# base-1.net
KiCad netlist of a schematic drawn in EAGLE
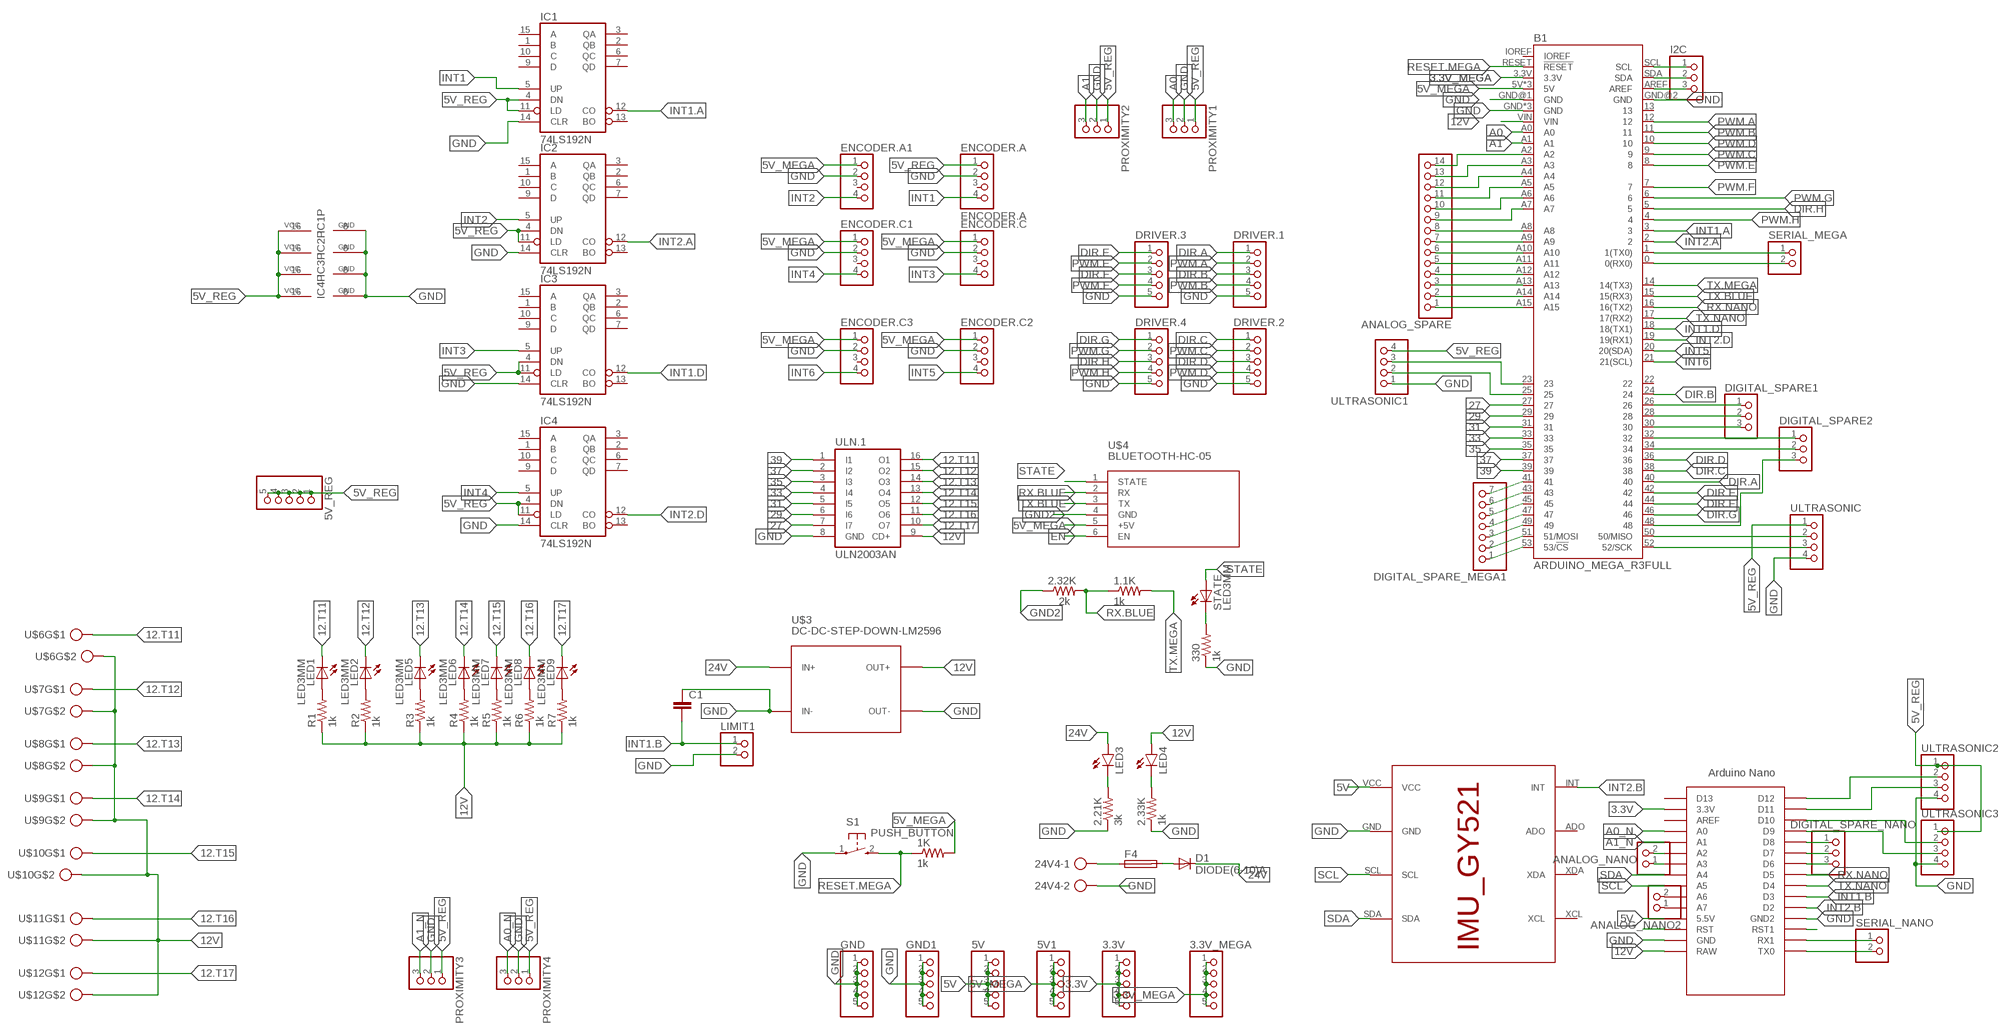
[diagram p0: schematic, sheet 1]

(export (version "E")
  (design (tool "Eeschema 10.0.6"))
  (components
    (comp (ref "1.1K")
      (value "1k")
      (footprint "eagle-import:0204_5")
      (libsource (lib "eagle-import") (part "RES-5"))
    )
    (comp (ref "1K")
      (value "1k")
      (footprint "eagle-import:0204_5")
      (libsource (lib "eagle-import") (part "RES-5"))
    )
    (comp (ref "2.21K")
      (value "3k")
      (footprint "eagle-import:0204_5")
      (libsource (lib "eagle-import") (part "RES-5"))
    )
    (comp (ref "2.32K")
      (value "2k")
      (footprint "eagle-import:0204_5")
      (libsource (lib "eagle-import") (part "RES-5"))
    )
    (comp (ref "2.33K")
      (value "1k")
      (footprint "eagle-import:0204_5")
      (libsource (lib "eagle-import") (part "RES-5"))
    )
    (comp (ref "3.3V")
      (value "PINHD-1X5")
      (footprint "eagle-import:1X05")
      (libsource (lib "eagle-import") (part "PINHD-1X5"))
    )
    (comp (ref "3.3V_MEGA")
      (value "PINHD-1X5")
      (footprint "eagle-import:1X05")
      (libsource (lib "eagle-import") (part "PINHD-1X5"))
    )
    (comp (ref "5V")
      (value "PINHD-1X5")
      (footprint "eagle-import:1X05")
      (libsource (lib "eagle-import") (part "PINHD-1X5"))
    )
    (comp (ref "5V1")
      (value "PINHD-1X5")
      (footprint "eagle-import:1X05")
      (libsource (lib "eagle-import") (part "PINHD-1X5"))
    )
    (comp (ref "5V_REG")
      (value "PINHD-1X5")
      (footprint "eagle-import:1X05")
      (libsource (lib "eagle-import") (part "PINHD-1X5"))
    )
    (comp (ref "24V4")
      (value "ROSTA.POWER")
      (footprint "eagle-import:W239-302")
      (libsource (lib "eagle-import") (part "ROSTA.POWER"))
    )
    (comp (ref "330")
      (value "1k")
      (footprint "eagle-import:0204_5")
      (libsource (lib "eagle-import") (part "RES-5"))
    )
    (comp (ref "ANALOG_NANO")
      (value "PINHD-1X2")
      (footprint "eagle-import:1X02")
      (libsource (lib "eagle-import") (part "PINHD-1X2"))
    )
    (comp (ref "ANALOG_NANO2")
      (value "PINHD-1X2")
      (footprint "eagle-import:1X02")
      (libsource (lib "eagle-import") (part "PINHD-1X2"))
    )
    (comp (ref "ANALOG_SPARE")
      (value "PINHD-1X14")
      (footprint "eagle-import:1X14")
      (libsource (lib "eagle-import") (part "PINHD-1X14"))
    )
    (comp (ref "B1")
      (value "ARDUINO_MEGA_R3FULL")
      (footprint "eagle-import:ARDUINO_MEGA_NO_SILK")
      (libsource (lib "eagle-import") (part "ARDUINO_MEGA_R3FULL"))
    )
    (comp (ref "C1")
      (value "CAPACITOR")
      (footprint "eagle-import:C025-025X050")
      (libsource (lib "eagle-import") (part "CAPACITOR"))
    )
    (comp (ref "D1")
      (value "DIODE(6-10)A")
      (footprint "eagle-import:DO201-15")
      (libsource (lib "eagle-import") (part "DIODE(6-10)A"))
    )
    (comp (ref "DIGITAL_SPARE1")
      (value "PINHD-1X3")
      (footprint "eagle-import:1X03")
      (libsource (lib "eagle-import") (part "PINHD-1X3"))
    )
    (comp (ref "DIGITAL_SPARE2")
      (value "PINHD-1X3")
      (footprint "eagle-import:1X03")
      (libsource (lib "eagle-import") (part "PINHD-1X3"))
    )
    (comp (ref "DIGITAL_SPARE_MEGA1")
      (value "PINHD-1X7")
      (footprint "eagle-import:1X07")
      (libsource (lib "eagle-import") (part "PINHD-1X7"))
    )
    (comp (ref "DIGITAL_SPARE_NANO")
      (value "PINHD-1X3")
      (footprint "eagle-import:1X03")
      (libsource (lib "eagle-import") (part "PINHD-1X3"))
    )
    (comp (ref "DRIVER.1")
      (value "PINHD-1X5")
      (footprint "eagle-import:1X05")
      (libsource (lib "eagle-import") (part "PINHD-1X5"))
    )
    (comp (ref "DRIVER.2")
      (value "PINHD-1X5")
      (footprint "eagle-import:1X05")
      (libsource (lib "eagle-import") (part "PINHD-1X5"))
    )
    (comp (ref "DRIVER.3")
      (value "PINHD-1X5")
      (footprint "eagle-import:1X05")
      (libsource (lib "eagle-import") (part "PINHD-1X5"))
    )
    (comp (ref "DRIVER.4")
      (value "PINHD-1X5")
      (footprint "eagle-import:1X05")
      (libsource (lib "eagle-import") (part "PINHD-1X5"))
    )
    (comp (ref "ENCODER.A")
      (value "ENCODER.A")
      (footprint "eagle-import:1X04")
      (libsource (lib "eagle-import") (part "PINHD-1X4"))
    )
    (comp (ref "ENCODER.A1")
      (value "PINHD-1X4")
      (footprint "eagle-import:1X04")
      (libsource (lib "eagle-import") (part "PINHD-1X4"))
    )
    (comp (ref "ENCODER.C")
      (value "PINHD-1X4")
      (footprint "eagle-import:1X04")
      (libsource (lib "eagle-import") (part "PINHD-1X4"))
    )
    (comp (ref "ENCODER.C1")
      (value "PINHD-1X4")
      (footprint "eagle-import:1X04")
      (libsource (lib "eagle-import") (part "PINHD-1X4"))
    )
    (comp (ref "ENCODER.C2")
      (value "PINHD-1X4")
      (footprint "eagle-import:1X04")
      (libsource (lib "eagle-import") (part "PINHD-1X4"))
    )
    (comp (ref "ENCODER.C3")
      (value "PINHD-1X4")
      (footprint "eagle-import:1X04")
      (libsource (lib "eagle-import") (part "PINHD-1X4"))
    )
    (comp (ref "F4")
      (value "FUSE_HOLDER")
      (footprint "eagle-import:SH22,5A")
      (libsource (lib "eagle-import") (part "FUSE_HOLDER"))
    )
    (comp (ref "GND")
      (value "PINHD-1X5")
      (footprint "eagle-import:1X05")
      (libsource (lib "eagle-import") (part "PINHD-1X5"))
    )
    (comp (ref "GND1")
      (value "PINHD-1X5")
      (footprint "eagle-import:1X05")
      (libsource (lib "eagle-import") (part "PINHD-1X5"))
    )
    (comp (ref "I2C")
      (value "PINHD-1X3")
      (footprint "eagle-import:1X03")
      (libsource (lib "eagle-import") (part "PINHD-1X3"))
    )
    (comp (ref "IC1")
      (value "74LS192N")
      (footprint "eagle-import:DIL16")
      (libsource (lib "eagle-import") (part "74192NLS"))
    )
    (comp (ref "IC2")
      (value "74LS192N")
      (footprint "eagle-import:DIL16")
      (libsource (lib "eagle-import") (part "74192NLS"))
    )
    (comp (ref "IC3")
      (value "74LS192N")
      (footprint "eagle-import:DIL16")
      (libsource (lib "eagle-import") (part "74192NLS"))
    )
    (comp (ref "IC4")
      (value "74LS192N")
      (footprint "eagle-import:DIL16")
      (libsource (lib "eagle-import") (part "74192NLS"))
    )
    (comp (ref "LED1")
      (value "LED3MM")
      (footprint "eagle-import:LED3MM")
      (libsource (lib "eagle-import") (part "LED3MM"))
    )
    (comp (ref "LED2")
      (value "LED3MM")
      (footprint "eagle-import:LED3MM")
      (libsource (lib "eagle-import") (part "LED3MM"))
    )
    (comp (ref "LED3")
      (value "LED5MM")
      (footprint "eagle-import:LED5MM")
      (libsource (lib "eagle-import") (part "LED5MM"))
    )
    (comp (ref "LED4")
      (value "LED5MM")
      (footprint "eagle-import:LED5MM")
      (libsource (lib "eagle-import") (part "LED5MM"))
    )
    (comp (ref "LED5")
      (value "LED3MM")
      (footprint "eagle-import:LED3MM")
      (libsource (lib "eagle-import") (part "LED3MM"))
    )
    (comp (ref "LED6")
      (value "LED3MM")
      (footprint "eagle-import:LED3MM")
      (libsource (lib "eagle-import") (part "LED3MM"))
    )
    (comp (ref "LED7")
      (value "LED3MM")
      (footprint "eagle-import:LED3MM")
      (libsource (lib "eagle-import") (part "LED3MM"))
    )
    (comp (ref "LED8")
      (value "LED3MM")
      (footprint "eagle-import:LED3MM")
      (libsource (lib "eagle-import") (part "LED3MM"))
    )
    (comp (ref "LED9")
      (value "LED3MM")
      (footprint "eagle-import:LED3MM")
      (libsource (lib "eagle-import") (part "LED3MM"))
    )
    (comp (ref "LIMIT1")
      (value "PINHD-1X2")
      (footprint "eagle-import:1X02")
      (libsource (lib "eagle-import") (part "PINHD-1X2"))
    )
    (comp (ref "PROXIMITY1")
      (value "PINHD-1X3")
      (footprint "eagle-import:1X03")
      (libsource (lib "eagle-import") (part "PINHD-1X3"))
    )
    (comp (ref "PROXIMITY2")
      (value "PINHD-1X3")
      (footprint "eagle-import:1X03")
      (libsource (lib "eagle-import") (part "PINHD-1X3"))
    )
    (comp (ref "PROXIMITY3")
      (value "PINHD-1X3")
      (footprint "eagle-import:1X03")
      (libsource (lib "eagle-import") (part "PINHD-1X3"))
    )
    (comp (ref "PROXIMITY4")
      (value "PINHD-1X3")
      (footprint "eagle-import:1X03")
      (libsource (lib "eagle-import") (part "PINHD-1X3"))
    )
    (comp (ref "R1")
      (value "1k")
      (footprint "eagle-import:0204_5")
      (libsource (lib "eagle-import") (part "RES-5"))
    )
    (comp (ref "R2")
      (value "1k")
      (footprint "eagle-import:0204_5")
      (libsource (lib "eagle-import") (part "RES-5"))
    )
    (comp (ref "R3")
      (value "1k")
      (footprint "eagle-import:0204_5")
      (libsource (lib "eagle-import") (part "RES-5"))
    )
    (comp (ref "R4")
      (value "1k")
      (footprint "eagle-import:0204_5")
      (libsource (lib "eagle-import") (part "RES-5"))
    )
    (comp (ref "R5")
      (value "1k")
      (footprint "eagle-import:0204_5")
      (libsource (lib "eagle-import") (part "RES-5"))
    )
    (comp (ref "R6")
      (value "1k")
      (footprint "eagle-import:0204_5")
      (libsource (lib "eagle-import") (part "RES-5"))
    )
    (comp (ref "R7")
      (value "1k")
      (footprint "eagle-import:0204_5")
      (libsource (lib "eagle-import") (part "RES-5"))
    )
    (comp (ref "S1")
      (value "PUSH_BUTTON")
      (footprint "eagle-import:B3F-10XX")
      (libsource (lib "eagle-import") (part "PUSH_BUTTON"))
    )
    (comp (ref "SERIAL_MEGA")
      (value "PINHD-1X2")
      (footprint "eagle-import:1X02")
      (libsource (lib "eagle-import") (part "PINHD-1X2"))
    )
    (comp (ref "SERIAL_NANO")
      (value "PINHD-1X2")
      (footprint "eagle-import:1X02")
      (libsource (lib "eagle-import") (part "PINHD-1X2"))
    )
    (comp (ref "STATE")
      (value "LED3MM")
      (footprint "eagle-import:LED3MM")
      (libsource (lib "eagle-import") (part "LED3MM"))
    )
    (comp (ref "U$1")
      (value "ARDUINO_NANO")
      (footprint "eagle-import:NANO")
      (libsource (lib "eagle-import") (part "ARDUINO_NANO"))
    )
    (comp (ref "U$3")
      (value "DC-DC-STEP-DOWN-LM2596")
      (footprint "eagle-import:DC-DC-STEP-DOWN-LM2596")
      (libsource (lib "eagle-import") (part "DC-DC-STEP-DOWN-LM2596"))
    )
    (comp (ref "U$4")
      (value "BLUETOOTH-HC-05")
      (footprint "eagle-import:WIRELESS-BLUETOOTH-HC-05")
      (libsource (lib "eagle-import") (part "BLUETOOTH-HC-05"))
    )
    (comp (ref "U$5")
      (value "IMU_ROBOCON_GY521")
      (footprint "eagle-import:IMU_GY521")
      (libsource (lib "eagle-import") (part "IMU_ROBOCON_GY521"))
    )
    (comp (ref "U$6")
      (value "CON_PTR_2")
      (footprint "eagle-import:AK300_2")
      (libsource (lib "eagle-import") (part "CON_PTR_2"))
    )
    (comp (ref "U$7")
      (value "CON_PTR_2")
      (footprint "eagle-import:AK300_2")
      (libsource (lib "eagle-import") (part "CON_PTR_2"))
    )
    (comp (ref "U$8")
      (value "CON_PTR_2")
      (footprint "eagle-import:AK300_2")
      (libsource (lib "eagle-import") (part "CON_PTR_2"))
    )
    (comp (ref "U$9")
      (value "CON_PTR_2")
      (footprint "eagle-import:AK300_2")
      (libsource (lib "eagle-import") (part "CON_PTR_2"))
    )
    (comp (ref "U$10")
      (value "CON_PTR_2")
      (footprint "eagle-import:AK300_2")
      (libsource (lib "eagle-import") (part "CON_PTR_2"))
    )
    (comp (ref "U$11")
      (value "CON_PTR_2")
      (footprint "eagle-import:AK300_2")
      (libsource (lib "eagle-import") (part "CON_PTR_2"))
    )
    (comp (ref "U$12")
      (value "CON_PTR_2")
      (footprint "eagle-import:AK300_2")
      (libsource (lib "eagle-import") (part "CON_PTR_2"))
    )
    (comp (ref "ULN.1")
      (value "ULN2003AN")
      (footprint "eagle-import:DIL16")
      (libsource (lib "eagle-import") (part "ULN2003AN"))
    )
    (comp (ref "ULTRASONIC")
      (value "PINHD-1X4")
      (footprint "eagle-import:1X04")
      (libsource (lib "eagle-import") (part "PINHD-1X4"))
    )
    (comp (ref "ULTRASONIC1")
      (value "PINHD-1X4")
      (footprint "eagle-import:1X04")
      (libsource (lib "eagle-import") (part "PINHD-1X4"))
    )
    (comp (ref "ULTRASONIC2")
      (value "PINHD-1X4")
      (footprint "eagle-import:1X04")
      (libsource (lib "eagle-import") (part "PINHD-1X4"))
    )
    (comp (ref "ULTRASONIC3")
      (value "PINHD-1X4")
      (footprint "eagle-import:1X04")
      (libsource (lib "eagle-import") (part "PINHD-1X4"))
    )
  )
  (nets
    (net (code "1") (name "3.3V") (class "Default")
      (node (ref "3.3V") (pin "1") (pinfunction "1_1") (pintype "passive"))
      (node (ref "3.3V") (pin "2") (pinfunction "2_2") (pintype "passive"))
      (node (ref "3.3V") (pin "3") (pinfunction "3_3") (pintype "passive"))
      (node (ref "3.3V") (pin "4") (pinfunction "4_4") (pintype "passive"))
      (node (ref "3.3V") (pin "5") (pinfunction "5_5") (pintype "passive"))
      (node (ref "U$1") (pin "3.3V") (pinfunction "3.3V_3.3V") (pintype "bidirectional"))
    )
    (net (code "2") (name "3.3V_MEGA") (class "Default")
      (node (ref "3.3V_MEGA") (pin "1") (pinfunction "1_1") (pintype "passive"))
      (node (ref "3.3V_MEGA") (pin "2") (pinfunction "2_2") (pintype "passive"))
      (node (ref "3.3V_MEGA") (pin "3") (pinfunction "3_3") (pintype "passive"))
      (node (ref "3.3V_MEGA") (pin "4") (pinfunction "4_4") (pintype "passive"))
      (node (ref "3.3V_MEGA") (pin "5") (pinfunction "5_5") (pintype "passive"))
      (node (ref "B1") (pin "3.3V") (pinfunction "3.3V_3.3V") (pintype "bidirectional"))
    )
    (net (code "3") (name "5V") (class "Default")
      (node (ref "5V") (pin "1") (pinfunction "1_1") (pintype "passive"))
      (node (ref "5V") (pin "2") (pinfunction "2_2") (pintype "passive"))
      (node (ref "5V") (pin "3") (pinfunction "3_3") (pintype "passive"))
      (node (ref "5V") (pin "4") (pinfunction "4_4") (pintype "passive"))
      (node (ref "5V") (pin "5") (pinfunction "5_5") (pintype "passive"))
      (node (ref "U$1") (pin "5V") (pinfunction "5.5V_5V") (pintype "bidirectional"))
      (node (ref "U$5") (pin "VCC") (pinfunction "VCC_VCC") (pintype "bidirectional"))
    )
    (net (code "4") (name "5V_MEGA") (class "Default")
      (node (ref "1K") (pin "2") (pinfunction "2_2") (pintype "passive"))
      (node (ref "5V1") (pin "1") (pinfunction "1_1") (pintype "passive"))
      (node (ref "5V1") (pin "2") (pinfunction "2_2") (pintype "passive"))
      (node (ref "5V1") (pin "3") (pinfunction "3_3") (pintype "passive"))
      (node (ref "5V1") (pin "4") (pinfunction "4_4") (pintype "passive"))
      (node (ref "5V1") (pin "5") (pinfunction "5_5") (pintype "passive"))
      (node (ref "B1") (pin "5V") (pinfunction "5V_5V") (pintype "bidirectional"))
      (node (ref "B1") (pin "5V@1") (pinfunction "5V_5V@1") (pintype "bidirectional"))
      (node (ref "B1") (pin "5V@2") (pinfunction "5V_5V@2") (pintype "bidirectional"))
      (node (ref "ENCODER.A1") (pin "1") (pinfunction "1_1") (pintype "passive"))
      (node (ref "ENCODER.C") (pin "1") (pinfunction "1_1") (pintype "passive"))
      (node (ref "ENCODER.C1") (pin "1") (pinfunction "1_1") (pintype "passive"))
      (node (ref "ENCODER.C2") (pin "1") (pinfunction "1_1") (pintype "passive"))
      (node (ref "ENCODER.C3") (pin "1") (pinfunction "1_1") (pintype "passive"))
      (node (ref "U$4") (pin "5") (pinfunction "+5V_5") (pintype "power_in"))
    )
    (net (code "5") (name "5V_REG") (class "Default")
      (node (ref "5V_REG") (pin "1") (pinfunction "1_1") (pintype "passive"))
      (node (ref "5V_REG") (pin "2") (pinfunction "2_2") (pintype "passive"))
      (node (ref "5V_REG") (pin "3") (pinfunction "3_3") (pintype "passive"))
      (node (ref "5V_REG") (pin "4") (pinfunction "4_4") (pintype "passive"))
      (node (ref "5V_REG") (pin "5") (pinfunction "5_5") (pintype "passive"))
      (node (ref "ENCODER.A") (pin "1") (pinfunction "1_1") (pintype "passive"))
      (node (ref "IC1") (pin "11") (pinfunction "LD_11") (pintype "input"))
      (node (ref "IC1") (pin "16") (pinfunction "VCC_16") (pintype "power_in"))
      (node (ref "IC1") (pin "4") (pinfunction "DN_4") (pintype "input"))
      (node (ref "IC2") (pin "11") (pinfunction "LD_11") (pintype "input"))
      (node (ref "IC2") (pin "16") (pinfunction "VCC_16") (pintype "power_in"))
      (node (ref "IC2") (pin "4") (pinfunction "DN_4") (pintype "input"))
      (node (ref "IC3") (pin "11") (pinfunction "LD_11") (pintype "input"))
      (node (ref "IC3") (pin "16") (pinfunction "VCC_16") (pintype "power_in"))
      (node (ref "IC3") (pin "4") (pinfunction "DN_4") (pintype "input"))
      (node (ref "IC4") (pin "11") (pinfunction "LD_11") (pintype "input"))
      (node (ref "IC4") (pin "16") (pinfunction "VCC_16") (pintype "power_in"))
      (node (ref "IC4") (pin "4") (pinfunction "DN_4") (pintype "input"))
      (node (ref "PROXIMITY1") (pin "1") (pinfunction "1_1") (pintype "passive"))
      (node (ref "PROXIMITY2") (pin "1") (pinfunction "1_1") (pintype "passive"))
      (node (ref "PROXIMITY3") (pin "1") (pinfunction "1_1") (pintype "passive"))
      (node (ref "PROXIMITY4") (pin "1") (pinfunction "1_1") (pintype "passive"))
      (node (ref "ULTRASONIC") (pin "1") (pinfunction "1_1") (pintype "passive"))
      (node (ref "ULTRASONIC1") (pin "4") (pinfunction "4_4") (pintype "passive"))
      (node (ref "ULTRASONIC2") (pin "1") (pinfunction "1_1") (pintype "passive"))
      (node (ref "ULTRASONIC3") (pin "1") (pinfunction "1_1") (pintype "passive"))
    )
    (net (code "6") (name "12.T11") (class "Default")
      (node (ref "LED1") (pin "K") (pinfunction "C_K") (pintype "passive"))
      (node (ref "U$6") (pin "1") (pinfunction "KL_1") (pintype "passive"))
      (node (ref "ULN.1") (pin "16") (pinfunction "O1_16") (pintype "open_collector"))
    )
    (net (code "7") (name "12.T12") (class "Default")
      (node (ref "LED2") (pin "K") (pinfunction "C_K") (pintype "passive"))
      (node (ref "U$7") (pin "1") (pinfunction "KL_1") (pintype "passive"))
      (node (ref "ULN.1") (pin "15") (pinfunction "O2_15") (pintype "open_collector"))
    )
    (net (code "8") (name "12.T13") (class "Default")
      (node (ref "LED5") (pin "K") (pinfunction "C_K") (pintype "passive"))
      (node (ref "U$8") (pin "1") (pinfunction "KL_1") (pintype "passive"))
      (node (ref "ULN.1") (pin "14") (pinfunction "O3_14") (pintype "open_collector"))
    )
    (net (code "9") (name "12.T14") (class "Default")
      (node (ref "LED6") (pin "K") (pinfunction "C_K") (pintype "passive"))
      (node (ref "U$9") (pin "1") (pinfunction "KL_1") (pintype "passive"))
      (node (ref "ULN.1") (pin "13") (pinfunction "O4_13") (pintype "open_collector"))
    )
    (net (code "10") (name "12.T15") (class "Default")
      (node (ref "LED7") (pin "K") (pinfunction "C_K") (pintype "passive"))
      (node (ref "U$10") (pin "1") (pinfunction "KL_1") (pintype "passive"))
      (node (ref "ULN.1") (pin "12") (pinfunction "O5_12") (pintype "open_collector"))
    )
    (net (code "11") (name "12.T16") (class "Default")
      (node (ref "LED8") (pin "K") (pinfunction "C_K") (pintype "passive"))
      (node (ref "U$11") (pin "1") (pinfunction "KL_1") (pintype "passive"))
      (node (ref "ULN.1") (pin "11") (pinfunction "O6_11") (pintype "open_collector"))
    )
    (net (code "12") (name "12.T17") (class "Default")
      (node (ref "LED9") (pin "K") (pinfunction "C_K") (pintype "passive"))
      (node (ref "U$12") (pin "1") (pinfunction "KL_1") (pintype "passive"))
      (node (ref "ULN.1") (pin "10") (pinfunction "O7_10") (pintype "open_collector"))
    )
    (net (code "13") (name "12V") (class "Default")
      (node (ref "B1") (pin "VIN") (pinfunction "VIN_VIN") (pintype "bidirectional"))
      (node (ref "LED4") (pin "A") (pinfunction "A_A") (pintype "passive"))
      (node (ref "R1") (pin "1") (pinfunction "1_1") (pintype "passive"))
      (node (ref "R2") (pin "1") (pinfunction "1_1") (pintype "passive"))
      (node (ref "R3") (pin "1") (pinfunction "1_1") (pintype "passive"))
      (node (ref "R4") (pin "1") (pinfunction "1_1") (pintype "passive"))
      (node (ref "R5") (pin "1") (pinfunction "1_1") (pintype "passive"))
      (node (ref "R6") (pin "1") (pinfunction "1_1") (pintype "passive"))
      (node (ref "R7") (pin "1") (pinfunction "1_1") (pintype "passive"))
      (node (ref "U$1") (pin "RAW") (pinfunction "RAW_RAW") (pintype "bidirectional"))
      (node (ref "U$10") (pin "2") (pinfunction "KL_2") (pintype "passive"))
      (node (ref "U$11") (pin "2") (pinfunction "KL_2") (pintype "passive"))
      (node (ref "U$12") (pin "2") (pinfunction "KL_2") (pintype "passive"))
      (node (ref "U$3") (pin "OUT+") (pinfunction "OUT+_OUT+") (pintype "bidirectional"))
      (node (ref "U$6") (pin "2") (pinfunction "KL_2") (pintype "passive"))
      (node (ref "U$7") (pin "2") (pinfunction "KL_2") (pintype "passive"))
      (node (ref "U$8") (pin "2") (pinfunction "KL_2") (pintype "passive"))
      (node (ref "U$9") (pin "2") (pinfunction "KL_2") (pintype "passive"))
      (node (ref "ULN.1") (pin "9") (pinfunction "CD+_9") (pintype "passive"))
    )
    (net (code "14") (name "24V") (class "Default")
      (node (ref "D1") (pin "C") (pinfunction "C_C") (pintype "passive"))
      (node (ref "LED3") (pin "A") (pinfunction "A_A") (pintype "passive"))
      (node (ref "U$3") (pin "IN+") (pinfunction "IN+_IN+") (pintype "bidirectional"))
    )
    (net (code "15") (name "27") (class "Default")
      (node (ref "B1") (pin "27") (pinfunction "27_27") (pintype "bidirectional"))
      (node (ref "ULN.1") (pin "7") (pinfunction "I7_7") (pintype "input"))
    )
    (net (code "16") (name "29") (class "Default")
      (node (ref "B1") (pin "29") (pinfunction "29_29") (pintype "bidirectional"))
      (node (ref "ULN.1") (pin "6") (pinfunction "I6_6") (pintype "input"))
    )
    (net (code "17") (name "31") (class "Default")
      (node (ref "B1") (pin "31") (pinfunction "31_31") (pintype "bidirectional"))
      (node (ref "ULN.1") (pin "5") (pinfunction "I5_5") (pintype "input"))
    )
    (net (code "18") (name "33") (class "Default")
      (node (ref "B1") (pin "33") (pinfunction "33_33") (pintype "bidirectional"))
      (node (ref "ULN.1") (pin "4") (pinfunction "I4_4") (pintype "input"))
    )
    (net (code "19") (name "35") (class "Default")
      (node (ref "B1") (pin "35") (pinfunction "35_35") (pintype "bidirectional"))
      (node (ref "ULN.1") (pin "3") (pinfunction "I3_3") (pintype "input"))
    )
    (net (code "20") (name "37") (class "Default")
      (node (ref "B1") (pin "37") (pinfunction "37_37") (pintype "bidirectional"))
      (node (ref "ULN.1") (pin "2") (pinfunction "I2_2") (pintype "input"))
    )
    (net (code "21") (name "39") (class "Default")
      (node (ref "B1") (pin "39") (pinfunction "39_39") (pintype "bidirectional"))
      (node (ref "ULN.1") (pin "1") (pinfunction "I1_1") (pintype "input"))
    )
    (net (code "22") (name "A0") (class "Default")
      (node (ref "B1") (pin "A0") (pinfunction "A0_A0") (pintype "bidirectional"))
      (node (ref "PROXIMITY1") (pin "3") (pinfunction "3_3") (pintype "passive"))
    )
    (net (code "23") (name "A0_N") (class "Default")
      (node (ref "PROXIMITY4") (pin "3") (pinfunction "3_3") (pintype "passive"))
      (node (ref "U$1") (pin "A0") (pinfunction "A0_A0") (pintype "bidirectional"))
    )
    (net (code "24") (name "A1") (class "Default")
      (node (ref "B1") (pin "A1") (pinfunction "A1_A1") (pintype "bidirectional"))
      (node (ref "PROXIMITY2") (pin "3") (pinfunction "3_3") (pintype "passive"))
    )
    (net (code "25") (name "A1_N") (class "Default")
      (node (ref "PROXIMITY3") (pin "3") (pinfunction "3_3") (pintype "passive"))
      (node (ref "U$1") (pin "A1") (pinfunction "A1_A1") (pintype "bidirectional"))
    )
    (net (code "26") (name "DIR.A") (class "Default")
      (node (ref "B1") (pin "40") (pinfunction "40_40") (pintype "bidirectional"))
      (node (ref "DRIVER.1") (pin "1") (pinfunction "1_1") (pintype "passive"))
    )
    (net (code "27") (name "DIR.B") (class "Default")
      (node (ref "B1") (pin "24") (pinfunction "24_24") (pintype "bidirectional"))
      (node (ref "DRIVER.1") (pin "3") (pinfunction "3_3") (pintype "passive"))
    )
    (net (code "28") (name "DIR.C") (class "Default")
      (node (ref "B1") (pin "38") (pinfunction "38_38") (pintype "bidirectional"))
      (node (ref "DRIVER.2") (pin "1") (pinfunction "1_1") (pintype "passive"))
    )
    (net (code "29") (name "DIR.D") (class "Default")
      (node (ref "B1") (pin "36") (pinfunction "36_36") (pintype "bidirectional"))
      (node (ref "DRIVER.2") (pin "3") (pinfunction "3_3") (pintype "passive"))
    )
    (net (code "30") (name "DIR.E") (class "Default")
      (node (ref "B1") (pin "42") (pinfunction "42_42") (pintype "bidirectional"))
      (node (ref "DRIVER.3") (pin "1") (pinfunction "1_1") (pintype "passive"))
    )
    (net (code "31") (name "DIR.F") (class "Default")
      (node (ref "B1") (pin "44") (pinfunction "44_44") (pintype "bidirectional"))
      (node (ref "DRIVER.3") (pin "3") (pinfunction "3_3") (pintype "passive"))
    )
    (net (code "32") (name "DIR.G") (class "Default")
      (node (ref "B1") (pin "46") (pinfunction "46_46") (pintype "bidirectional"))
      (node (ref "DRIVER.4") (pin "1") (pinfunction "1_1") (pintype "passive"))
    )
    (net (code "33") (name "DIR.H") (class "Default")
      (node (ref "B1") (pin "5") (pinfunction "5_5") (pintype "bidirectional"))
      (node (ref "DRIVER.4") (pin "3") (pinfunction "3_3") (pintype "passive"))
    )
    (net (code "34") (name "EN") (class "Default")
      (node (ref "U$4") (pin "6") (pinfunction "EN_6") (pintype "bidirectional"))
    )
    (net (code "35") (name "GND") (class "Default")
      (node (ref "2.21K") (pin "1") (pinfunction "1_1") (pintype "passive"))
      (node (ref "2.33K") (pin "1") (pinfunction "1_1") (pintype "passive"))
      (node (ref "24V4") (pin "2") (pinfunction "KL_2") (pintype "passive"))
      (node (ref "330") (pin "1") (pinfunction "1_1") (pintype "passive"))
      (node (ref "B1") (pin "GND") (pinfunction "GND_GND") (pintype "bidirectional"))
      (node (ref "B1") (pin "GND@1") (pinfunction "GND_GND@1") (pintype "bidirectional"))
      (node (ref "B1") (pin "GND@2") (pinfunction "GND_GND@2") (pintype "bidirectional"))
      (node (ref "B1") (pin "GND@3") (pinfunction "GND_GND@3") (pintype "bidirectional"))
      (node (ref "B1") (pin "GND@4") (pinfunction "GND_GND@4") (pintype "bidirectional"))
      (node (ref "C1") (pin "1") (pinfunction "1_1") (pintype "passive"))
      (node (ref "DRIVER.1") (pin "5") (pinfunction "5_5") (pintype "passive"))
      (node (ref "DRIVER.2") (pin "5") (pinfunction "5_5") (pintype "passive"))
      (node (ref "DRIVER.3") (pin "5") (pinfunction "5_5") (pintype "passive"))
      (node (ref "DRIVER.4") (pin "5") (pinfunction "5_5") (pintype "passive"))
      (node (ref "ENCODER.A") (pin "2") (pinfunction "2_2") (pintype "passive"))
      (node (ref "ENCODER.A1") (pin "2") (pinfunction "2_2") (pintype "passive"))
      (node (ref "ENCODER.C") (pin "2") (pinfunction "2_2") (pintype "passive"))
      (node (ref "ENCODER.C1") (pin "2") (pinfunction "2_2") (pintype "passive"))
      (node (ref "ENCODER.C2") (pin "2") (pinfunction "2_2") (pintype "passive"))
      (node (ref "ENCODER.C3") (pin "2") (pinfunction "2_2") (pintype "passive"))
      (node (ref "GND") (pin "1") (pinfunction "1_1") (pintype "passive"))
      (node (ref "GND") (pin "2") (pinfunction "2_2") (pintype "passive"))
      (node (ref "GND") (pin "3") (pinfunction "3_3") (pintype "passive"))
      (node (ref "GND") (pin "4") (pinfunction "4_4") (pintype "passive"))
      (node (ref "GND") (pin "5") (pinfunction "5_5") (pintype "passive"))
      (node (ref "GND1") (pin "1") (pinfunction "1_1") (pintype "passive"))
      (node (ref "GND1") (pin "2") (pinfunction "2_2") (pintype "passive"))
      (node (ref "GND1") (pin "3") (pinfunction "3_3") (pintype "passive"))
      (node (ref "GND1") (pin "4") (pinfunction "4_4") (pintype "passive"))
      (node (ref "GND1") (pin "5") (pinfunction "5_5") (pintype "passive"))
      (node (ref "IC1") (pin "14") (pinfunction "CLR_14") (pintype "input"))
      (node (ref "IC1") (pin "8") (pinfunction "GND_8") (pintype "power_in"))
      (node (ref "IC2") (pin "14") (pinfunction "CLR_14") (pintype "input"))
      (node (ref "IC2") (pin "8") (pinfunction "GND_8") (pintype "power_in"))
      (node (ref "IC3") (pin "14") (pinfunction "CLR_14") (pintype "input"))
      (node (ref "IC3") (pin "8") (pinfunction "GND_8") (pintype "power_in"))
      (node (ref "IC4") (pin "14") (pinfunction "CLR_14") (pintype "input"))
      (node (ref "IC4") (pin "8") (pinfunction "GND_8") (pintype "power_in"))
      (node (ref "LIMIT1") (pin "2") (pinfunction "2_2") (pintype "passive"))
      (node (ref "PROXIMITY1") (pin "2") (pinfunction "2_2") (pintype "passive"))
      (node (ref "PROXIMITY2") (pin "2") (pinfunction "2_2") (pintype "passive"))
      (node (ref "PROXIMITY3") (pin "2") (pinfunction "2_2") (pintype "passive"))
      (node (ref "PROXIMITY4") (pin "2") (pinfunction "2_2") (pintype "passive"))
      (node (ref "S1") (pin "1") (pinfunction "P_1") (pintype "passive"))
      (node (ref "U$1") (pin "GND") (pinfunction "GND_GND") (pintype "bidirectional"))
      (node (ref "U$1") (pin "GND1") (pinfunction "GND2_GND1") (pintype "bidirectional"))
      (node (ref "U$3") (pin "IN-") (pinfunction "IN-_IN-") (pintype "bidirectional"))
      (node (ref "U$3") (pin "OUT-") (pinfunction "OUT-_OUT-") (pintype "bidirectional"))
      (node (ref "U$5") (pin "GND") (pinfunction "GND_GND") (pintype "bidirectional"))
      (node (ref "ULN.1") (pin "8") (pinfunction "GND_8") (pintype "power_in"))
      (node (ref "ULTRASONIC") (pin "4") (pinfunction "4_4") (pintype "passive"))
      (node (ref "ULTRASONIC1") (pin "1") (pinfunction "1_1") (pintype "passive"))
      (node (ref "ULTRASONIC2") (pin "4") (pinfunction "4_4") (pintype "passive"))
      (node (ref "ULTRASONIC3") (pin "4") (pinfunction "4_4") (pintype "passive"))
    )
    (net (code "36") (name "GND2") (class "Default")
      (node (ref "2.32K") (pin "1") (pinfunction "1_1") (pintype "passive"))
      (node (ref "U$4") (pin "4") (pinfunction "GND_4") (pintype "power_in"))
    )
    (net (code "37") (name "INT1") (class "Default")
      (node (ref "ENCODER.A") (pin "4") (pinfunction "4_4") (pintype "passive"))
      (node (ref "IC1") (pin "5") (pinfunction "UP_5") (pintype "input"))
    )
    (net (code "38") (name "INT1.A") (class "Default")
      (node (ref "B1") (pin "3") (pinfunction "3_3") (pintype "bidirectional"))
      (node (ref "IC1") (pin "12") (pinfunction "CO_12") (pintype "output"))
    )
    (net (code "39") (name "INT1.B") (class "Default")
      (node (ref "C1") (pin "2") (pinfunction "2_2") (pintype "passive"))
      (node (ref "LIMIT1") (pin "1") (pinfunction "1_1") (pintype "passive"))
      (node (ref "U$1") (pin "D3") (pinfunction "D3_D3") (pintype "bidirectional"))
    )
    (net (code "40") (name "INT1.D") (class "Default")
      (node (ref "B1") (pin "18") (pinfunction "18(TX1)_18") (pintype "bidirectional"))
      (node (ref "IC3") (pin "12") (pinfunction "CO_12") (pintype "output"))
    )
    (net (code "41") (name "INT2") (class "Default")
      (node (ref "ENCODER.A1") (pin "4") (pinfunction "4_4") (pintype "passive"))
      (node (ref "IC2") (pin "5") (pinfunction "UP_5") (pintype "input"))
    )
    (net (code "42") (name "INT2.A") (class "Default")
      (node (ref "B1") (pin "2") (pinfunction "2_2") (pintype "bidirectional"))
      (node (ref "IC2") (pin "12") (pinfunction "CO_12") (pintype "output"))
    )
    (net (code "43") (name "INT2.B") (class "Default")
      (node (ref "U$1") (pin "D2") (pinfunction "D2_D2") (pintype "bidirectional"))
      (node (ref "U$5") (pin "INT") (pinfunction "INT_INT") (pintype "bidirectional"))
    )
    (net (code "44") (name "INT2.D") (class "Default")
      (node (ref "B1") (pin "19") (pinfunction "19(RX1)_19") (pintype "bidirectional"))
      (node (ref "IC4") (pin "12") (pinfunction "CO_12") (pintype "output"))
    )
    (net (code "45") (name "INT3") (class "Default")
      (node (ref "ENCODER.C") (pin "4") (pinfunction "4_4") (pintype "passive"))
      (node (ref "IC3") (pin "5") (pinfunction "UP_5") (pintype "input"))
    )
    (net (code "46") (name "INT4") (class "Default")
      (node (ref "ENCODER.C1") (pin "4") (pinfunction "4_4") (pintype "passive"))
      (node (ref "IC4") (pin "5") (pinfunction "UP_5") (pintype "input"))
    )
    (net (code "47") (name "INT5") (class "Default")
      (node (ref "B1") (pin "20") (pinfunction "20(SDA)_20") (pintype "bidirectional"))
      (node (ref "ENCODER.C2") (pin "4") (pinfunction "4_4") (pintype "passive"))
    )
    (net (code "48") (name "INT6") (class "Default")
      (node (ref "B1") (pin "21") (pinfunction "21(SCL)_21") (pintype "bidirectional"))
      (node (ref "ENCODER.C3") (pin "4") (pinfunction "4_4") (pintype "passive"))
    )
    (net (code "49") (name "Net-(24V4A-KL)") (class "Default")
      (node (ref "24V4") (pin "1") (pinfunction "KL_1") (pintype "passive"))
      (node (ref "F4") (pin "1") (pinfunction "1_1") (pintype "passive"))
    )
    (net (code "50") (name "Net-(ANALOG_NANO-Pad1)") (class "Default")
      (node (ref "ANALOG_NANO") (pin "1") (pinfunction "1_1") (pintype "passive"))
      (node (ref "U$1") (pin "A3") (pinfunction "A3_A3") (pintype "bidirectional"))
    )
    (net (code "51") (name "Net-(ANALOG_NANO-Pad2)") (class "Default")
      (node (ref "ANALOG_NANO") (pin "2") (pinfunction "2_2") (pintype "passive"))
      (node (ref "U$1") (pin "A2") (pinfunction "A2_A2") (pintype "bidirectional"))
    )
    (net (code "52") (name "Net-(ANALOG_NANO2-Pad1)") (class "Default")
      (node (ref "ANALOG_NANO2") (pin "1") (pinfunction "1_1") (pintype "passive"))
      (node (ref "U$1") (pin "A7") (pinfunction "A7_A7") (pintype "bidirectional"))
    )
    (net (code "53") (name "Net-(ANALOG_NANO2-Pad2)") (class "Default")
      (node (ref "ANALOG_NANO2") (pin "2") (pinfunction "2_2") (pintype "passive"))
      (node (ref "U$1") (pin "A6") (pinfunction "A6_A6") (pintype "bidirectional"))
    )
    (net (code "54") (name "Net-(ANALOG_SPARE-Pad1)") (class "Default")
      (node (ref "ANALOG_SPARE") (pin "1") (pinfunction "1_1") (pintype "passive"))
      (node (ref "B1") (pin "A15") (pinfunction "A15_A15") (pintype "bidirectional"))
    )
    (net (code "55") (name "Net-(ANALOG_SPARE-Pad2)") (class "Default")
      (node (ref "ANALOG_SPARE") (pin "2") (pinfunction "2_2") (pintype "passive"))
      (node (ref "B1") (pin "A14") (pinfunction "A14_A14") (pintype "bidirectional"))
    )
    (net (code "56") (name "Net-(ANALOG_SPARE-Pad3)") (class "Default")
      (node (ref "ANALOG_SPARE") (pin "3") (pinfunction "3_3") (pintype "passive"))
      (node (ref "B1") (pin "A13") (pinfunction "A13_A13") (pintype "bidirectional"))
    )
    (net (code "57") (name "Net-(ANALOG_SPARE-Pad4)") (class "Default")
      (node (ref "ANALOG_SPARE") (pin "4") (pinfunction "4_4") (pintype "passive"))
      (node (ref "B1") (pin "A12") (pinfunction "A12_A12") (pintype "bidirectional"))
    )
    (net (code "58") (name "Net-(ANALOG_SPARE-Pad5)") (class "Default")
      (node (ref "ANALOG_SPARE") (pin "5") (pinfunction "5_5") (pintype "passive"))
      (node (ref "B1") (pin "A11") (pinfunction "A11_A11") (pintype "bidirectional"))
    )
    (net (code "59") (name "Net-(ANALOG_SPARE-Pad6)") (class "Default")
      (node (ref "ANALOG_SPARE") (pin "6") (pinfunction "6_6") (pintype "passive"))
      (node (ref "B1") (pin "A10") (pinfunction "A10_A10") (pintype "bidirectional"))
    )
    (net (code "60") (name "Net-(ANALOG_SPARE-Pad7)") (class "Default")
      (node (ref "ANALOG_SPARE") (pin "7") (pinfunction "7_7") (pintype "passive"))
      (node (ref "B1") (pin "A9") (pinfunction "A9_A9") (pintype "bidirectional"))
    )
    (net (code "61") (name "Net-(ANALOG_SPARE-Pad8)") (class "Default")
      (node (ref "ANALOG_SPARE") (pin "8") (pinfunction "8_8") (pintype "passive"))
      (node (ref "B1") (pin "A8") (pinfunction "A8_A8") (pintype "bidirectional"))
    )
    (net (code "62") (name "Net-(ANALOG_SPARE-Pad9)") (class "Default")
      (node (ref "ANALOG_SPARE") (pin "9") (pinfunction "9_9") (pintype "passive"))
      (node (ref "B1") (pin "A7") (pinfunction "A7_A7") (pintype "bidirectional"))
    )
    (net (code "63") (name "Net-(ANALOG_SPARE-Pad10)") (class "Default")
      (node (ref "ANALOG_SPARE") (pin "10") (pinfunction "10_10") (pintype "passive"))
      (node (ref "B1") (pin "A6") (pinfunction "A6_A6") (pintype "bidirectional"))
    )
    (net (code "64") (name "Net-(ANALOG_SPARE-Pad11)") (class "Default")
      (node (ref "ANALOG_SPARE") (pin "11") (pinfunction "11_11") (pintype "passive"))
      (node (ref "B1") (pin "A5") (pinfunction "A5_A5") (pintype "bidirectional"))
    )
    (net (code "65") (name "Net-(ANALOG_SPARE-Pad12)") (class "Default")
      (node (ref "ANALOG_SPARE") (pin "12") (pinfunction "12_12") (pintype "passive"))
      (node (ref "B1") (pin "A4") (pinfunction "A4_A4") (pintype "bidirectional"))
    )
    (net (code "66") (name "Net-(ANALOG_SPARE-Pad13)") (class "Default")
      (node (ref "ANALOG_SPARE") (pin "13") (pinfunction "13_13") (pintype "passive"))
      (node (ref "B1") (pin "A3") (pinfunction "A3_A3") (pintype "bidirectional"))
    )
    (net (code "67") (name "Net-(ANALOG_SPARE-Pad14)") (class "Default")
      (node (ref "ANALOG_SPARE") (pin "14") (pinfunction "14_14") (pintype "passive"))
      (node (ref "B1") (pin "A2") (pinfunction "A2_A2") (pintype "bidirectional"))
    )
    (net (code "68") (name "Net-(B1-0(RX0))") (class "Default")
      (node (ref "B1") (pin "0") (pinfunction "0(RX0)_0") (pintype "bidirectional"))
      (node (ref "SERIAL_MEGA") (pin "2") (pinfunction "2_2") (pintype "passive"))
    )
    (net (code "69") (name "Net-(B1-1(TX0))") (class "Default")
      (node (ref "B1") (pin "1") (pinfunction "1(TX0)_1") (pintype "bidirectional"))
      (node (ref "SERIAL_MEGA") (pin "1") (pinfunction "1_1") (pintype "passive"))
    )
    (net (code "70") (name "Net-(B1-50{slash}MISO)") (class "Default")
      (node (ref "B1") (pin "50") (pinfunction "50/MISO_50") (pintype "bidirectional"))
      (node (ref "ULTRASONIC") (pin "2") (pinfunction "2_2") (pintype "passive"))
    )
    (net (code "71") (name "Net-(B1-51{slash}MOSI)") (class "Default")
      (node (ref "B1") (pin "51") (pinfunction "51/MOSI_51") (pintype "bidirectional"))
      (node (ref "DIGITAL_SPARE_MEGA1") (pin "2") (pinfunction "2_2") (pintype "passive"))
    )
    (net (code "72") (name "Net-(B1-52{slash}SCK)") (class "Default")
      (node (ref "B1") (pin "52") (pinfunction "52/SCK_52") (pintype "bidirectional"))
      (node (ref "ULTRASONIC") (pin "3") (pinfunction "3_3") (pintype "passive"))
    )
    (net (code "73") (name "Net-(B1-53{slash}~{CS})") (class "Default")
      (node (ref "B1") (pin "53") (pinfunction "53/~{CS}_53") (pintype "bidirectional"))
      (node (ref "DIGITAL_SPARE_MEGA1") (pin "1") (pinfunction "1_1") (pintype "passive"))
    )
    (net (code "74") (name "Net-(B1-Pad23)") (class "Default")
      (node (ref "B1") (pin "23") (pinfunction "23_23") (pintype "bidirectional"))
      (node (ref "ULTRASONIC1") (pin "3") (pinfunction "3_3") (pintype "passive"))
    )
    (net (code "75") (name "Net-(B1-Pad25)") (class "Default")
      (node (ref "B1") (pin "25") (pinfunction "25_25") (pintype "bidirectional"))
      (node (ref "ULTRASONIC1") (pin "2") (pinfunction "2_2") (pintype "passive"))
    )
    (net (code "76") (name "Net-(B1-Pad26)") (class "Default")
      (node (ref "B1") (pin "26") (pinfunction "26_26") (pintype "bidirectional"))
      (node (ref "DIGITAL_SPARE1") (pin "1") (pinfunction "1_1") (pintype "passive"))
    )
    (net (code "77") (name "Net-(B1-Pad28)") (class "Default")
      (node (ref "B1") (pin "28") (pinfunction "28_28") (pintype "bidirectional"))
      (node (ref "DIGITAL_SPARE1") (pin "2") (pinfunction "2_2") (pintype "passive"))
    )
    (net (code "78") (name "Net-(B1-Pad30)") (class "Default")
      (node (ref "B1") (pin "30") (pinfunction "30_30") (pintype "bidirectional"))
      (node (ref "DIGITAL_SPARE1") (pin "3") (pinfunction "3_3") (pintype "passive"))
    )
    (net (code "79") (name "Net-(B1-Pad32)") (class "Default")
      (node (ref "B1") (pin "32") (pinfunction "32_32") (pintype "bidirectional"))
      (node (ref "DIGITAL_SPARE2") (pin "1") (pinfunction "1_1") (pintype "passive"))
    )
    (net (code "80") (name "Net-(B1-Pad34)") (class "Default")
      (node (ref "B1") (pin "34") (pinfunction "34_34") (pintype "bidirectional"))
      (node (ref "DIGITAL_SPARE2") (pin "2") (pinfunction "2_2") (pintype "passive"))
    )
    (net (code "81") (name "Net-(B1-Pad41)") (class "Default")
      (node (ref "B1") (pin "41") (pinfunction "41_41") (pintype "bidirectional"))
      (node (ref "DIGITAL_SPARE_MEGA1") (pin "7") (pinfunction "7_7") (pintype "passive"))
    )
    (net (code "82") (name "Net-(B1-Pad43)") (class "Default")
      (node (ref "B1") (pin "43") (pinfunction "43_43") (pintype "bidirectional"))
      (node (ref "DIGITAL_SPARE_MEGA1") (pin "6") (pinfunction "6_6") (pintype "passive"))
    )
    (net (code "83") (name "Net-(B1-Pad45)") (class "Default")
      (node (ref "B1") (pin "45") (pinfunction "45_45") (pintype "bidirectional"))
      (node (ref "DIGITAL_SPARE_MEGA1") (pin "5") (pinfunction "5_5") (pintype "passive"))
    )
    (net (code "84") (name "Net-(B1-Pad47)") (class "Default")
      (node (ref "B1") (pin "47") (pinfunction "47_47") (pintype "bidirectional"))
      (node (ref "DIGITAL_SPARE_MEGA1") (pin "4") (pinfunction "4_4") (pintype "passive"))
    )
    (net (code "85") (name "Net-(B1-Pad48)") (class "Default")
      (node (ref "B1") (pin "48") (pinfunction "48_48") (pintype "bidirectional"))
      (node (ref "DIGITAL_SPARE2") (pin "3") (pinfunction "3_3") (pintype "passive"))
    )
    (net (code "86") (name "Net-(B1-Pad49)") (class "Default")
      (node (ref "B1") (pin "49") (pinfunction "49_49") (pintype "bidirectional"))
      (node (ref "DIGITAL_SPARE_MEGA1") (pin "3") (pinfunction "3_3") (pintype "passive"))
    )
    (net (code "87") (name "Net-(B1-PadAREF)") (class "Default")
      (node (ref "B1") (pin "AREF") (pinfunction "AREF_AREF") (pintype "bidirectional"))
      (node (ref "I2C") (pin "3") (pinfunction "3_3") (pintype "passive"))
    )
    (net (code "88") (name "Net-(B1-PadSCL)") (class "Default")
      (node (ref "B1") (pin "SCL") (pinfunction "SCL_SCL") (pintype "bidirectional"))
      (node (ref "I2C") (pin "1") (pinfunction "1_1") (pintype "passive"))
    )
    (net (code "89") (name "Net-(B1-PadSDA)") (class "Default")
      (node (ref "B1") (pin "SDA") (pinfunction "SDA_SDA") (pintype "bidirectional"))
      (node (ref "I2C") (pin "2") (pinfunction "2_2") (pintype "passive"))
    )
    (net (code "90") (name "Net-(D1-PadA)") (class "Default")
      (node (ref "D1") (pin "A") (pinfunction "A_A") (pintype "passive"))
      (node (ref "F4") (pin "2") (pinfunction "2_2") (pintype "passive"))
    )
    (net (code "91") (name "Net-(DIGITAL_SPARE_NANO-Pad1)") (class "Default")
      (node (ref "DIGITAL_SPARE_NANO") (pin "1") (pinfunction "1_1") (pintype "passive"))
      (node (ref "U$1") (pin "D8") (pinfunction "D8_D8") (pintype "bidirectional"))
    )
    (net (code "92") (name "Net-(DIGITAL_SPARE_NANO-Pad2)") (class "Default")
      (node (ref "DIGITAL_SPARE_NANO") (pin "2") (pinfunction "2_2") (pintype "passive"))
      (node (ref "U$1") (pin "D7") (pinfunction "D7_D7") (pintype "bidirectional"))
    )
    (net (code "93") (name "Net-(DIGITAL_SPARE_NANO-Pad3)") (class "Default")
      (node (ref "DIGITAL_SPARE_NANO") (pin "3") (pinfunction "3_3") (pintype "passive"))
      (node (ref "U$1") (pin "D6") (pinfunction "D6_D6") (pintype "bidirectional"))
    )
    (net (code "94") (name "Net-(LED1-PadA)") (class "Default")
      (node (ref "LED1") (pin "A") (pinfunction "A_A") (pintype "passive"))
      (node (ref "R1") (pin "2") (pinfunction "2_2") (pintype "passive"))
    )
    (net (code "95") (name "Net-(LED2-PadA)") (class "Default")
      (node (ref "LED2") (pin "A") (pinfunction "A_A") (pintype "passive"))
      (node (ref "R2") (pin "2") (pinfunction "2_2") (pintype "passive"))
    )
    (net (code "96") (name "Net-(LED3-C)") (class "Default")
      (node (ref "2.21K") (pin "2") (pinfunction "2_2") (pintype "passive"))
      (node (ref "LED3") (pin "K") (pinfunction "C_K") (pintype "passive"))
    )
    (net (code "97") (name "Net-(LED4-C)") (class "Default")
      (node (ref "2.33K") (pin "2") (pinfunction "2_2") (pintype "passive"))
      (node (ref "LED4") (pin "K") (pinfunction "C_K") (pintype "passive"))
    )
    (net (code "98") (name "Net-(LED5-PadA)") (class "Default")
      (node (ref "LED5") (pin "A") (pinfunction "A_A") (pintype "passive"))
      (node (ref "R3") (pin "2") (pinfunction "2_2") (pintype "passive"))
    )
    (net (code "99") (name "Net-(LED6-PadA)") (class "Default")
      (node (ref "LED6") (pin "A") (pinfunction "A_A") (pintype "passive"))
      (node (ref "R4") (pin "2") (pinfunction "2_2") (pintype "passive"))
    )
    (net (code "100") (name "Net-(LED7-PadA)") (class "Default")
      (node (ref "LED7") (pin "A") (pinfunction "A_A") (pintype "passive"))
      (node (ref "R5") (pin "2") (pinfunction "2_2") (pintype "passive"))
    )
    (net (code "101") (name "Net-(LED8-PadA)") (class "Default")
      (node (ref "LED8") (pin "A") (pinfunction "A_A") (pintype "passive"))
      (node (ref "R6") (pin "2") (pinfunction "2_2") (pintype "passive"))
    )
    (net (code "102") (name "Net-(LED9-PadA)") (class "Default")
      (node (ref "LED9") (pin "A") (pinfunction "A_A") (pintype "passive"))
      (node (ref "R7") (pin "2") (pinfunction "2_2") (pintype "passive"))
    )
    (net (code "103") (name "Net-(SERIAL_NANO-Pad1)") (class "Default")
      (node (ref "SERIAL_NANO") (pin "1") (pinfunction "1_1") (pintype "passive"))
      (node (ref "U$1") (pin "RX1") (pinfunction "RX1_RX1") (pintype "bidirectional"))
    )
    (net (code "104") (name "Net-(SERIAL_NANO-Pad2)") (class "Default")
      (node (ref "SERIAL_NANO") (pin "2") (pinfunction "2_2") (pintype "passive"))
      (node (ref "U$1") (pin "TX0") (pinfunction "TX0_TX0") (pintype "bidirectional"))
    )
    (net (code "105") (name "Net-(STATE-C)") (class "Default")
      (node (ref "330") (pin "2") (pinfunction "2_2") (pintype "passive"))
      (node (ref "STATE") (pin "K") (pinfunction "C_K") (pintype "passive"))
    )
    (net (code "106") (name "Net-(U$1-PadD9)") (class "Default")
      (node (ref "U$1") (pin "D9") (pinfunction "D9_D9") (pintype "bidirectional"))
      (node (ref "ULTRASONIC3") (pin "3") (pinfunction "3_3") (pintype "passive"))
    )
    (net (code "107") (name "Net-(U$1-PadD10)") (class "Default")
      (node (ref "U$1") (pin "D10") (pinfunction "D10_D10") (pintype "bidirectional"))
      (node (ref "ULTRASONIC3") (pin "2") (pinfunction "2_2") (pintype "passive"))
    )
    (net (code "108") (name "Net-(U$1-PadD11)") (class "Default")
      (node (ref "U$1") (pin "D11") (pinfunction "D11_D11") (pintype "bidirectional"))
      (node (ref "ULTRASONIC2") (pin "3") (pinfunction "3_3") (pintype "passive"))
    )
    (net (code "109") (name "Net-(U$1-PadD12)") (class "Default")
      (node (ref "U$1") (pin "D12") (pinfunction "D12_D12") (pintype "bidirectional"))
      (node (ref "ULTRASONIC2") (pin "2") (pinfunction "2_2") (pintype "passive"))
    )
    (net (code "110") (name "PWM.A") (class "Default")
      (node (ref "B1") (pin "12") (pinfunction "12_12") (pintype "bidirectional"))
      (node (ref "DRIVER.1") (pin "2") (pinfunction "2_2") (pintype "passive"))
    )
    (net (code "111") (name "PWM.B") (class "Default")
      (node (ref "B1") (pin "11") (pinfunction "11_11") (pintype "bidirectional"))
      (node (ref "DRIVER.1") (pin "4") (pinfunction "4_4") (pintype "passive"))
    )
    (net (code "112") (name "PWM.C") (class "Default")
      (node (ref "B1") (pin "9") (pinfunction "9_9") (pintype "bidirectional"))
      (node (ref "DRIVER.2") (pin "2") (pinfunction "2_2") (pintype "passive"))
    )
    (net (code "113") (name "PWM.D") (class "Default")
      (node (ref "B1") (pin "10") (pinfunction "10_10") (pintype "bidirectional"))
      (node (ref "DRIVER.2") (pin "4") (pinfunction "4_4") (pintype "passive"))
    )
    (net (code "114") (name "PWM.E") (class "Default")
      (node (ref "B1") (pin "8") (pinfunction "8_8") (pintype "bidirectional"))
      (node (ref "DRIVER.3") (pin "2") (pinfunction "2_2") (pintype "passive"))
    )
    (net (code "115") (name "PWM.F") (class "Default")
      (node (ref "B1") (pin "7") (pinfunction "7_7") (pintype "bidirectional"))
      (node (ref "DRIVER.3") (pin "4") (pinfunction "4_4") (pintype "passive"))
    )
    (net (code "116") (name "PWM.G") (class "Default")
      (node (ref "B1") (pin "6") (pinfunction "6_6") (pintype "bidirectional"))
      (node (ref "DRIVER.4") (pin "2") (pinfunction "2_2") (pintype "passive"))
    )
    (net (code "117") (name "PWM.H") (class "Default")
      (node (ref "B1") (pin "4") (pinfunction "4_4") (pintype "bidirectional"))
      (node (ref "DRIVER.4") (pin "4") (pinfunction "4_4") (pintype "passive"))
    )
    (net (code "118") (name "RESET.MEGA") (class "Default")
      (node (ref "1K") (pin "1") (pinfunction "1_1") (pintype "passive"))
      (node (ref "B1") (pin "RESET") (pinfunction "~{RESET}_RESET") (pintype "bidirectional"))
      (node (ref "S1") (pin "2") (pinfunction "S_2") (pintype "passive"))
    )
    (net (code "119") (name "RX.BLUE") (class "Default")
      (node (ref "1.1K") (pin "1") (pinfunction "1_1") (pintype "passive"))
      (node (ref "2.32K") (pin "2") (pinfunction "2_2") (pintype "passive"))
      (node (ref "U$4") (pin "2") (pinfunction "RX_2") (pintype "bidirectional"))
    )
    (net (code "120") (name "RX.NANO") (class "Default")
      (node (ref "B1") (pin "16") (pinfunction "16(TX2)_16") (pintype "bidirectional"))
      (node (ref "U$1") (pin "D5") (pinfunction "D5_D5") (pintype "bidirectional"))
    )
    (net (code "121") (name "SCL") (class "Default")
      (node (ref "U$1") (pin "A5") (pinfunction "A5_A5") (pintype "bidirectional"))
      (node (ref "U$5") (pin "SCL") (pinfunction "SCL_SCL") (pintype "bidirectional"))
    )
    (net (code "122") (name "SDA") (class "Default")
      (node (ref "U$1") (pin "A4") (pinfunction "A4_A4") (pintype "bidirectional"))
      (node (ref "U$5") (pin "SDA") (pinfunction "SDA_SDA") (pintype "bidirectional"))
    )
    (net (code "123") (name "STATE") (class "Default")
      (node (ref "STATE") (pin "A") (pinfunction "A_A") (pintype "passive"))
      (node (ref "U$4") (pin "1") (pinfunction "STATE_1") (pintype "bidirectional"))
    )
    (net (code "124") (name "TX.BLUE") (class "Default")
      (node (ref "B1") (pin "15") (pinfunction "15(RX3)_15") (pintype "bidirectional"))
      (node (ref "U$4") (pin "3") (pinfunction "TX_3") (pintype "bidirectional"))
    )
    (net (code "125") (name "TX.MEGA") (class "Default")
      (node (ref "1.1K") (pin "2") (pinfunction "2_2") (pintype "passive"))
      (node (ref "B1") (pin "14") (pinfunction "14(TX3)_14") (pintype "bidirectional"))
    )
    (net (code "126") (name "TX.NANO") (class "Default")
      (node (ref "B1") (pin "17") (pinfunction "17(RX2)_17") (pintype "bidirectional"))
      (node (ref "U$1") (pin "D4") (pinfunction "D4_D4") (pintype "bidirectional"))
    )
    (net (code "127") (name "unconnected-(B1-Pad13)") (class "Default")
      (node (ref "B1") (pin "13") (pinfunction "13_13") (pintype "bidirectional"))
    )
    (net (code "128") (name "unconnected-(B1-Pad22)") (class "Default")
      (node (ref "B1") (pin "22") (pinfunction "22_22") (pintype "bidirectional"))
    )
    (net (code "129") (name "unconnected-(B1-PadIOREF)") (class "Default")
      (node (ref "B1") (pin "IOREF") (pinfunction "IOREF_IOREF") (pintype "bidirectional"))
    )
    (net (code "130") (name "unconnected-(ENCODER.A-Pad3)") (class "Default")
      (node (ref "ENCODER.A") (pin "3") (pinfunction "3_3") (pintype "passive"))
    )
    (net (code "131") (name "unconnected-(ENCODER.A1-Pad3)") (class "Default")
      (node (ref "ENCODER.A1") (pin "3") (pinfunction "3_3") (pintype "passive"))
    )
    (net (code "132") (name "unconnected-(ENCODER.C-Pad3)") (class "Default")
      (node (ref "ENCODER.C") (pin "3") (pinfunction "3_3") (pintype "passive"))
    )
    (net (code "133") (name "unconnected-(ENCODER.C1-Pad3)") (class "Default")
      (node (ref "ENCODER.C1") (pin "3") (pinfunction "3_3") (pintype "passive"))
    )
    (net (code "134") (name "unconnected-(ENCODER.C2-Pad3)") (class "Default")
      (node (ref "ENCODER.C2") (pin "3") (pinfunction "3_3") (pintype "passive"))
    )
    (net (code "135") (name "unconnected-(ENCODER.C3-Pad3)") (class "Default")
      (node (ref "ENCODER.C3") (pin "3") (pinfunction "3_3") (pintype "passive"))
    )
    (net (code "136") (name "unconnected-(IC1A-A-Pad15)") (class "Default")
      (node (ref "IC1") (pin "15") (pinfunction "A_15") (pintype "input"))
    )
    (net (code "137") (name "unconnected-(IC1A-B-Pad1)") (class "Default")
      (node (ref "IC1") (pin "1") (pinfunction "B_1") (pintype "input"))
    )
    (net (code "138") (name "unconnected-(IC1A-BO-Pad13)") (class "Default")
      (node (ref "IC1") (pin "13") (pinfunction "BO_13") (pintype "output"))
    )
    (net (code "139") (name "unconnected-(IC1A-C-Pad10)") (class "Default")
      (node (ref "IC1") (pin "10") (pinfunction "C_10") (pintype "input"))
    )
    (net (code "140") (name "unconnected-(IC1A-D-Pad9)") (class "Default")
      (node (ref "IC1") (pin "9") (pinfunction "D_9") (pintype "input"))
    )
    (net (code "141") (name "unconnected-(IC1A-QA-Pad3)") (class "Default")
      (node (ref "IC1") (pin "3") (pinfunction "QA_3") (pintype "output"))
    )
    (net (code "142") (name "unconnected-(IC1A-QB-Pad2)") (class "Default")
      (node (ref "IC1") (pin "2") (pinfunction "QB_2") (pintype "output"))
    )
    (net (code "143") (name "unconnected-(IC1A-QC-Pad6)") (class "Default")
      (node (ref "IC1") (pin "6") (pinfunction "QC_6") (pintype "output"))
    )
    (net (code "144") (name "unconnected-(IC1A-QD-Pad7)") (class "Default")
      (node (ref "IC1") (pin "7") (pinfunction "QD_7") (pintype "output"))
    )
    (net (code "145") (name "unconnected-(IC2A-A-Pad15)") (class "Default")
      (node (ref "IC2") (pin "15") (pinfunction "A_15") (pintype "input"))
    )
    (net (code "146") (name "unconnected-(IC2A-B-Pad1)") (class "Default")
      (node (ref "IC2") (pin "1") (pinfunction "B_1") (pintype "input"))
    )
    (net (code "147") (name "unconnected-(IC2A-BO-Pad13)") (class "Default")
      (node (ref "IC2") (pin "13") (pinfunction "BO_13") (pintype "output"))
    )
    (net (code "148") (name "unconnected-(IC2A-C-Pad10)") (class "Default")
      (node (ref "IC2") (pin "10") (pinfunction "C_10") (pintype "input"))
    )
    (net (code "149") (name "unconnected-(IC2A-D-Pad9)") (class "Default")
      (node (ref "IC2") (pin "9") (pinfunction "D_9") (pintype "input"))
    )
    (net (code "150") (name "unconnected-(IC2A-QA-Pad3)") (class "Default")
      (node (ref "IC2") (pin "3") (pinfunction "QA_3") (pintype "output"))
    )
    (net (code "151") (name "unconnected-(IC2A-QB-Pad2)") (class "Default")
      (node (ref "IC2") (pin "2") (pinfunction "QB_2") (pintype "output"))
    )
    (net (code "152") (name "unconnected-(IC2A-QC-Pad6)") (class "Default")
      (node (ref "IC2") (pin "6") (pinfunction "QC_6") (pintype "output"))
    )
    (net (code "153") (name "unconnected-(IC2A-QD-Pad7)") (class "Default")
      (node (ref "IC2") (pin "7") (pinfunction "QD_7") (pintype "output"))
    )
    (net (code "154") (name "unconnected-(IC3A-A-Pad15)") (class "Default")
      (node (ref "IC3") (pin "15") (pinfunction "A_15") (pintype "input"))
    )
    (net (code "155") (name "unconnected-(IC3A-B-Pad1)") (class "Default")
      (node (ref "IC3") (pin "1") (pinfunction "B_1") (pintype "input"))
    )
    (net (code "156") (name "unconnected-(IC3A-BO-Pad13)") (class "Default")
      (node (ref "IC3") (pin "13") (pinfunction "BO_13") (pintype "output"))
    )
    (net (code "157") (name "unconnected-(IC3A-C-Pad10)") (class "Default")
      (node (ref "IC3") (pin "10") (pinfunction "C_10") (pintype "input"))
    )
    (net (code "158") (name "unconnected-(IC3A-D-Pad9)") (class "Default")
      (node (ref "IC3") (pin "9") (pinfunction "D_9") (pintype "input"))
    )
    (net (code "159") (name "unconnected-(IC3A-QA-Pad3)") (class "Default")
      (node (ref "IC3") (pin "3") (pinfunction "QA_3") (pintype "output"))
    )
    (net (code "160") (name "unconnected-(IC3A-QB-Pad2)") (class "Default")
      (node (ref "IC3") (pin "2") (pinfunction "QB_2") (pintype "output"))
    )
    (net (code "161") (name "unconnected-(IC3A-QC-Pad6)") (class "Default")
      (node (ref "IC3") (pin "6") (pinfunction "QC_6") (pintype "output"))
    )
    (net (code "162") (name "unconnected-(IC3A-QD-Pad7)") (class "Default")
      (node (ref "IC3") (pin "7") (pinfunction "QD_7") (pintype "output"))
    )
    (net (code "163") (name "unconnected-(IC4A-A-Pad15)") (class "Default")
      (node (ref "IC4") (pin "15") (pinfunction "A_15") (pintype "input"))
    )
    (net (code "164") (name "unconnected-(IC4A-B-Pad1)") (class "Default")
      (node (ref "IC4") (pin "1") (pinfunction "B_1") (pintype "input"))
    )
    (net (code "165") (name "unconnected-(IC4A-BO-Pad13)") (class "Default")
      (node (ref "IC4") (pin "13") (pinfunction "BO_13") (pintype "output"))
    )
    (net (code "166") (name "unconnected-(IC4A-C-Pad10)") (class "Default")
      (node (ref "IC4") (pin "10") (pinfunction "C_10") (pintype "input"))
    )
    (net (code "167") (name "unconnected-(IC4A-D-Pad9)") (class "Default")
      (node (ref "IC4") (pin "9") (pinfunction "D_9") (pintype "input"))
    )
    (net (code "168") (name "unconnected-(IC4A-QA-Pad3)") (class "Default")
      (node (ref "IC4") (pin "3") (pinfunction "QA_3") (pintype "output"))
    )
    (net (code "169") (name "unconnected-(IC4A-QB-Pad2)") (class "Default")
      (node (ref "IC4") (pin "2") (pinfunction "QB_2") (pintype "output"))
    )
    (net (code "170") (name "unconnected-(IC4A-QC-Pad6)") (class "Default")
      (node (ref "IC4") (pin "6") (pinfunction "QC_6") (pintype "output"))
    )
    (net (code "171") (name "unconnected-(IC4A-QD-Pad7)") (class "Default")
      (node (ref "IC4") (pin "7") (pinfunction "QD_7") (pintype "output"))
    )
    (net (code "172") (name "unconnected-(U$1-PadAREF)") (class "Default")
      (node (ref "U$1") (pin "AREF") (pinfunction "AREF_AREF") (pintype "bidirectional"))
    )
    (net (code "173") (name "unconnected-(U$1-PadD13)") (class "Default")
      (node (ref "U$1") (pin "D13") (pinfunction "D13_D13") (pintype "bidirectional"))
    )
    (net (code "174") (name "unconnected-(U$1-PadRST)") (class "Default")
      (node (ref "U$1") (pin "RST") (pinfunction "RST_RST") (pintype "bidirectional"))
    )
    (net (code "175") (name "unconnected-(U$1-PadRST1)") (class "Default")
      (node (ref "U$1") (pin "RST1") (pinfunction "RST1_RST1") (pintype "bidirectional"))
    )
    (net (code "176") (name "unconnected-(U$5-PadADO)") (class "Default")
      (node (ref "U$5") (pin "ADO") (pinfunction "ADO_ADO") (pintype "bidirectional"))
    )
    (net (code "177") (name "unconnected-(U$5-PadXCL)") (class "Default")
      (node (ref "U$5") (pin "XCL") (pinfunction "XCL_XCL") (pintype "bidirectional"))
    )
    (net (code "178") (name "unconnected-(U$5-PadXDA)") (class "Default")
      (node (ref "U$5") (pin "XDA") (pinfunction "XDA_XDA") (pintype "bidirectional"))
    )
  )
)
